# ExtensionConnector.net
KiCad netlist of a schematic drawn in Altium Designer
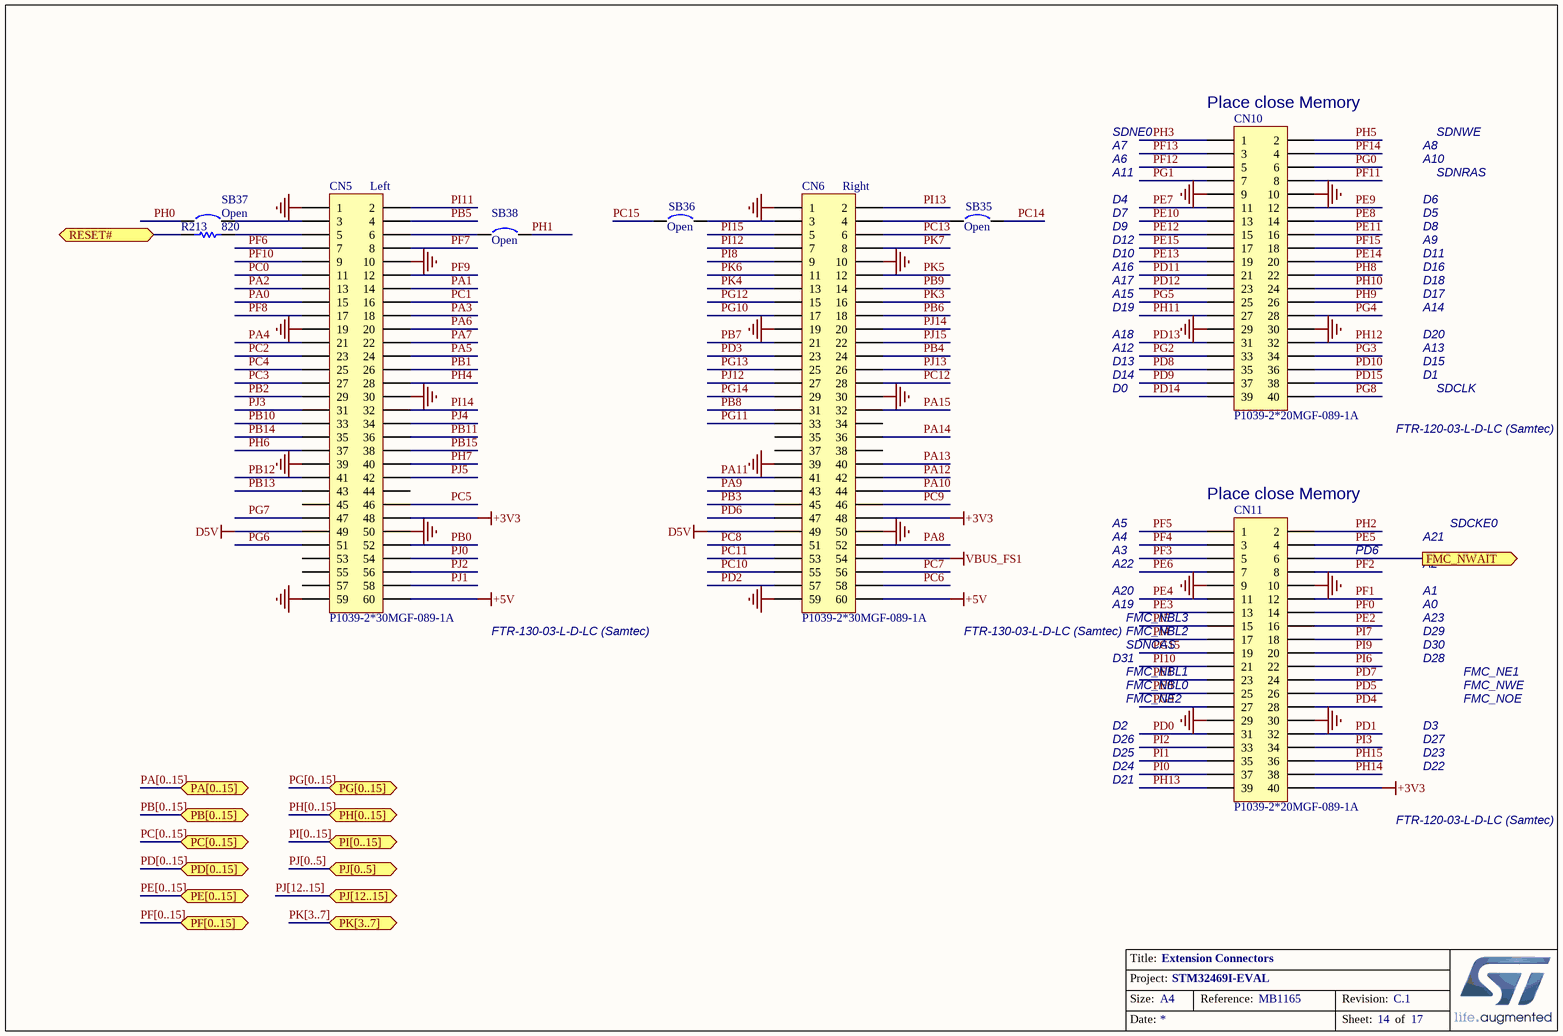
[diagram p0: ExtensionConnector.SchDoc]

(export (version "E")
  (design (tool "Eeschema 10.0.6"))
  (components
    (comp (ref "CN5")
      (value "P1039-2*30MGF-089-1A")
      (footprint "FTR-130-53-L-D-LC")
      (description "Header, 40-Pin, Dual row")
      (fields (field (name "PUBLISHER") "Altium Limited"))
      (libsource (lib "mb1045") (part "FTR-130-53-L-D-LC"))
    )
    (comp (ref "CN6")
      (value "P1039-2*30MGF-089-1A")
      (footprint "FTR-130-53-L-D-LC")
      (description "Header, 40-Pin, Dual row")
      (fields (field (name "PUBLISHER") "Altium Limited"))
      (libsource (lib "mb1045") (part "FTR-130-53-L-D-LC"))
    )
    (comp (ref "CN10")
      (value "P1039-2*20MGF-089-1A")
      (footprint "FTR-120-53-L-D-LC")
      (description "Header, 20-Pin, Dual row")
      (fields (field (name "PUBLISHER") "Altium Limited"))
      (libsource (lib "mb1045") (part "FTR-120-53-L-D-LC"))
    )
    (comp (ref "CN11")
      (value "P1039-2*20MGF-089-1A")
      (footprint "FTR-120-53-L-D-LC")
      (description "Header, 20-Pin, Dual row")
      (fields (field (name "PUBLISHER") "Altium Limited"))
      (libsource (lib "mb1045") (part "FTR-120-53-L-D-LC"))
    )
    (comp (ref "R213")
      (value "820")
      (footprint "0603R")
      (description "Resistor")
      (fields (field (name "PUBLISHER") "Altium Limited"))
      (libsource (lib "Miscellaneous Devices") (part "res1"))
    )
    (comp (ref "SB35")
      (value "Open")
      (footprint "SB_0603")
      (description "Circuit Breaker")
      (fields (field (name "PUBLISHER") "Altium Limited"))
      (libsource (lib "MB1165") (part "Circuit Breaker"))
    )
    (comp (ref "SB36")
      (value "Open")
      (footprint "SB_0603")
      (description "Circuit Breaker")
      (fields (field (name "PUBLISHER") "Altium Limited"))
      (libsource (lib "") (part "Circuit Breaker_1"))
    )
    (comp (ref "SB37")
      (value "Open")
      (footprint "SB_0603")
      (description "Circuit Breaker")
      (fields (field (name "PUBLISHER") "Altium Limited"))
      (libsource (lib "") (part "Circuit Breaker_1"))
    )
    (comp (ref "SB38")
      (value "Open")
      (footprint "SB_0603")
      (description "Circuit Breaker")
      (fields (field (name "PUBLISHER") "Altium Limited"))
      (libsource (lib "MB1165") (part "Circuit Breaker"))
    )
  )
  (nets
    (net (code "1") (name "+3V3") (class "Default")
      (node (ref "CN11") (pin "40") (pinfunction "40_40") (pintype "passive"))
      (node (ref "CN5") (pin "48") (pinfunction "48_48") (pintype "passive"))
      (node (ref "CN6") (pin "48") (pinfunction "48_48") (pintype "passive"))
    )
    (net (code "2") (name "+5V") (class "Default")
      (node (ref "CN5") (pin "60") (pinfunction "60_60") (pintype "passive"))
      (node (ref "CN6") (pin "60") (pinfunction "60_60") (pintype "passive"))
    )
    (net (code "3") (name "/FMC_NWAIT") (class "Default")
      (node (ref "CN11") (pin "6") (pinfunction "6_6") (pintype "passive"))
    )
    (net (code "4") (name "/PA0") (class "Default")
      (node (ref "CN5") (pin "15") (pinfunction "15_15") (pintype "passive"))
    )
    (net (code "5") (name "/PA1") (class "Default")
      (node (ref "CN5") (pin "14") (pinfunction "14_14") (pintype "passive"))
    )
    (net (code "6") (name "/PA2") (class "Default")
      (node (ref "CN5") (pin "13") (pinfunction "13_13") (pintype "passive"))
    )
    (net (code "7") (name "/PA3") (class "Default")
      (node (ref "CN5") (pin "18") (pinfunction "18_18") (pintype "passive"))
    )
    (net (code "8") (name "/PA4") (class "Default")
      (node (ref "CN5") (pin "21") (pinfunction "21_21") (pintype "passive"))
    )
    (net (code "9") (name "/PA5") (class "Default")
      (node (ref "CN5") (pin "24") (pinfunction "24_24") (pintype "passive"))
    )
    (net (code "10") (name "/PA6") (class "Default")
      (node (ref "CN5") (pin "20") (pinfunction "20_20") (pintype "passive"))
    )
    (net (code "11") (name "/PA7") (class "Default")
      (node (ref "CN5") (pin "22") (pinfunction "22_22") (pintype "passive"))
    )
    (net (code "12") (name "/PA8") (class "Default")
      (node (ref "CN6") (pin "52") (pinfunction "52_52") (pintype "passive"))
    )
    (net (code "13") (name "/PA9") (class "Default")
      (node (ref "CN6") (pin "43") (pinfunction "43_43") (pintype "passive"))
    )
    (net (code "14") (name "/PA10") (class "Default")
      (node (ref "CN6") (pin "44") (pinfunction "44_44") (pintype "passive"))
    )
    (net (code "15") (name "/PA11") (class "Default")
      (node (ref "CN6") (pin "41") (pinfunction "41_41") (pintype "passive"))
    )
    (net (code "16") (name "/PA12") (class "Default")
      (node (ref "CN6") (pin "42") (pinfunction "42_42") (pintype "passive"))
    )
    (net (code "17") (name "/PA13") (class "Default")
      (node (ref "CN6") (pin "40") (pinfunction "40_40") (pintype "passive"))
    )
    (net (code "18") (name "/PA14") (class "Default")
      (node (ref "CN6") (pin "36") (pinfunction "36_36") (pintype "passive"))
    )
    (net (code "19") (name "/PA15") (class "Default")
      (node (ref "CN6") (pin "32") (pinfunction "32_32") (pintype "passive"))
    )
    (net (code "21") (name "/PB0") (class "Default")
      (node (ref "CN5") (pin "52") (pinfunction "52_52") (pintype "passive"))
    )
    (net (code "22") (name "/PB1") (class "Default")
      (node (ref "CN5") (pin "26") (pinfunction "26_26") (pintype "passive"))
    )
    (net (code "23") (name "/PB2") (class "Default")
      (node (ref "CN5") (pin "29") (pinfunction "29_29") (pintype "passive"))
    )
    (net (code "24") (name "/PB3") (class "Default")
      (node (ref "CN6") (pin "45") (pinfunction "45_45") (pintype "passive"))
    )
    (net (code "25") (name "/PB4") (class "Default")
      (node (ref "CN6") (pin "24") (pinfunction "24_24") (pintype "passive"))
    )
    (net (code "26") (name "/PB5") (class "Default")
      (node (ref "CN5") (pin "4") (pinfunction "4_4") (pintype "passive"))
    )
    (net (code "27") (name "/PB6") (class "Default")
      (node (ref "CN6") (pin "18") (pinfunction "18_18") (pintype "passive"))
    )
    (net (code "28") (name "/PB7") (class "Default")
      (node (ref "CN6") (pin "21") (pinfunction "21_21") (pintype "passive"))
    )
    (net (code "29") (name "/PB8") (class "Default")
      (node (ref "CN6") (pin "31") (pinfunction "31_31") (pintype "passive"))
    )
    (net (code "30") (name "/PB9") (class "Default")
      (node (ref "CN6") (pin "14") (pinfunction "14_14") (pintype "passive"))
    )
    (net (code "31") (name "/PB10") (class "Default")
      (node (ref "CN5") (pin "33") (pinfunction "33_33") (pintype "passive"))
    )
    (net (code "32") (name "/PB11") (class "Default")
      (node (ref "CN5") (pin "36") (pinfunction "36_36") (pintype "passive"))
    )
    (net (code "33") (name "/PB12") (class "Default")
      (node (ref "CN5") (pin "41") (pinfunction "41_41") (pintype "passive"))
    )
    (net (code "34") (name "/PB13") (class "Default")
      (node (ref "CN5") (pin "43") (pinfunction "43_43") (pintype "passive"))
    )
    (net (code "35") (name "/PB14") (class "Default")
      (node (ref "CN5") (pin "35") (pinfunction "35_35") (pintype "passive"))
    )
    (net (code "36") (name "/PB15") (class "Default")
      (node (ref "CN5") (pin "38") (pinfunction "38_38") (pintype "passive"))
    )
    (net (code "38") (name "/PC0") (class "Default")
      (node (ref "CN5") (pin "11") (pinfunction "11_11") (pintype "passive"))
    )
    (net (code "39") (name "/PC1") (class "Default")
      (node (ref "CN5") (pin "16") (pinfunction "16_16") (pintype "passive"))
    )
    (net (code "40") (name "/PC2") (class "Default")
      (node (ref "CN5") (pin "23") (pinfunction "23_23") (pintype "passive"))
    )
    (net (code "41") (name "/PC3") (class "Default")
      (node (ref "CN5") (pin "27") (pinfunction "27_27") (pintype "passive"))
    )
    (net (code "42") (name "/PC4") (class "Default")
      (node (ref "CN5") (pin "25") (pinfunction "25_25") (pintype "passive"))
    )
    (net (code "43") (name "/PC5") (class "Default")
      (node (ref "CN5") (pin "46") (pinfunction "46_46") (pintype "passive"))
    )
    (net (code "44") (name "/PC6") (class "Default")
      (node (ref "CN6") (pin "58") (pinfunction "58_58") (pintype "passive"))
    )
    (net (code "45") (name "/PC7") (class "Default")
      (node (ref "CN6") (pin "56") (pinfunction "56_56") (pintype "passive"))
    )
    (net (code "46") (name "/PC8") (class "Default")
      (node (ref "CN6") (pin "51") (pinfunction "51_51") (pintype "passive"))
    )
    (net (code "47") (name "/PC9") (class "Default")
      (node (ref "CN6") (pin "46") (pinfunction "46_46") (pintype "passive"))
    )
    (net (code "48") (name "/PC10") (class "Default")
      (node (ref "CN6") (pin "55") (pinfunction "55_55") (pintype "passive"))
    )
    (net (code "49") (name "/PC11") (class "Default")
      (node (ref "CN6") (pin "53") (pinfunction "53_53") (pintype "passive"))
    )
    (net (code "50") (name "/PC12") (class "Default")
      (node (ref "CN6") (pin "28") (pinfunction "28_28") (pintype "passive"))
    )
    (net (code "51") (name "/PC13") (class "Default")
      (node (ref "CN6") (pin "6") (pinfunction "6_6") (pintype "passive"))
    )
    (net (code "52") (name "/PC14") (class "Default")
      (node (ref "SB35") (pin "1") (pinfunction "1_1") (pintype "passive"))
    )
    (net (code "53") (name "/PC15") (class "Default")
      (node (ref "SB36") (pin "1") (pinfunction "1_1") (pintype "passive"))
    )
    (net (code "55") (name "/PD0") (class "Default")
      (node (ref "CN11") (pin "31") (pinfunction "31_31") (pintype "passive"))
    )
    (net (code "56") (name "/PD1") (class "Default")
      (node (ref "CN11") (pin "32") (pinfunction "32_32") (pintype "passive"))
    )
    (net (code "57") (name "/PD2") (class "Default")
      (node (ref "CN6") (pin "57") (pinfunction "57_57") (pintype "passive"))
    )
    (net (code "58") (name "/PD3") (class "Default")
      (node (ref "CN6") (pin "23") (pinfunction "23_23") (pintype "passive"))
    )
    (net (code "59") (name "/PD4") (class "Default")
      (node (ref "CN11") (pin "28") (pinfunction "28_28") (pintype "passive"))
    )
    (net (code "60") (name "/PD5") (class "Default")
      (node (ref "CN11") (pin "26") (pinfunction "26_26") (pintype "passive"))
    )
    (net (code "61") (name "/PD6") (class "Default")
      (node (ref "CN6") (pin "47") (pinfunction "47_47") (pintype "passive"))
    )
    (net (code "62") (name "/PD7") (class "Default")
      (node (ref "CN11") (pin "24") (pinfunction "24_24") (pintype "passive"))
    )
    (net (code "63") (name "/PD8") (class "Default")
      (node (ref "CN10") (pin "35") (pinfunction "35_35") (pintype "passive"))
    )
    (net (code "64") (name "/PD9") (class "Default")
      (node (ref "CN10") (pin "37") (pinfunction "37_37") (pintype "passive"))
    )
    (net (code "65") (name "/PD10") (class "Default")
      (node (ref "CN10") (pin "36") (pinfunction "36_36") (pintype "passive"))
    )
    (net (code "66") (name "/PD11") (class "Default")
      (node (ref "CN10") (pin "21") (pinfunction "21_21") (pintype "passive"))
    )
    (net (code "67") (name "/PD12") (class "Default")
      (node (ref "CN10") (pin "23") (pinfunction "23_23") (pintype "passive"))
    )
    (net (code "68") (name "/PD13") (class "Default")
      (node (ref "CN10") (pin "31") (pinfunction "31_31") (pintype "passive"))
    )
    (net (code "69") (name "/PD14") (class "Default")
      (node (ref "CN10") (pin "39") (pinfunction "39_39") (pintype "passive"))
    )
    (net (code "70") (name "/PD15") (class "Default")
      (node (ref "CN10") (pin "38") (pinfunction "38_38") (pintype "passive"))
    )
    (net (code "72") (name "/PE0") (class "Default")
      (node (ref "CN11") (pin "25") (pinfunction "25_25") (pintype "passive"))
    )
    (net (code "73") (name "/PE1") (class "Default")
      (node (ref "CN11") (pin "23") (pinfunction "23_23") (pintype "passive"))
    )
    (net (code "74") (name "/PE2") (class "Default")
      (node (ref "CN11") (pin "16") (pinfunction "16_16") (pintype "passive"))
    )
    (net (code "75") (name "/PE3") (class "Default")
      (node (ref "CN11") (pin "13") (pinfunction "13_13") (pintype "passive"))
    )
    (net (code "76") (name "/PE4") (class "Default")
      (node (ref "CN11") (pin "11") (pinfunction "11_11") (pintype "passive"))
    )
    (net (code "77") (name "/PE5") (class "Default")
      (node (ref "CN11") (pin "4") (pinfunction "4_4") (pintype "passive"))
    )
    (net (code "78") (name "/PE6") (class "Default")
      (node (ref "CN11") (pin "7") (pinfunction "7_7") (pintype "passive"))
    )
    (net (code "79") (name "/PE7") (class "Default")
      (node (ref "CN10") (pin "11") (pinfunction "11_11") (pintype "passive"))
    )
    (net (code "80") (name "/PE8") (class "Default")
      (node (ref "CN10") (pin "14") (pinfunction "14_14") (pintype "passive"))
    )
    (net (code "81") (name "/PE9") (class "Default")
      (node (ref "CN10") (pin "12") (pinfunction "12_12") (pintype "passive"))
    )
    (net (code "82") (name "/PE10") (class "Default")
      (node (ref "CN10") (pin "13") (pinfunction "13_13") (pintype "passive"))
    )
    (net (code "83") (name "/PE11") (class "Default")
      (node (ref "CN10") (pin "16") (pinfunction "16_16") (pintype "passive"))
    )
    (net (code "84") (name "/PE12") (class "Default")
      (node (ref "CN10") (pin "15") (pinfunction "15_15") (pintype "passive"))
    )
    (net (code "85") (name "/PE13") (class "Default")
      (node (ref "CN10") (pin "19") (pinfunction "19_19") (pintype "passive"))
    )
    (net (code "86") (name "/PE14") (class "Default")
      (node (ref "CN10") (pin "20") (pinfunction "20_20") (pintype "passive"))
    )
    (net (code "87") (name "/PE15") (class "Default")
      (node (ref "CN10") (pin "17") (pinfunction "17_17") (pintype "passive"))
    )
    (net (code "89") (name "/PF0") (class "Default")
      (node (ref "CN11") (pin "14") (pinfunction "14_14") (pintype "passive"))
    )
    (net (code "90") (name "/PF1") (class "Default")
      (node (ref "CN11") (pin "12") (pinfunction "12_12") (pintype "passive"))
    )
    (net (code "91") (name "/PF2") (class "Default")
      (node (ref "CN11") (pin "8") (pinfunction "8_8") (pintype "passive"))
    )
    (net (code "92") (name "/PF3") (class "Default")
      (node (ref "CN11") (pin "5") (pinfunction "5_5") (pintype "passive"))
    )
    (net (code "93") (name "/PF4") (class "Default")
      (node (ref "CN11") (pin "3") (pinfunction "3_3") (pintype "passive"))
    )
    (net (code "94") (name "/PF5") (class "Default")
      (node (ref "CN11") (pin "1") (pinfunction "1_1") (pintype "passive"))
    )
    (net (code "95") (name "/PF6") (class "Default")
      (node (ref "CN5") (pin "7") (pinfunction "7_7") (pintype "passive"))
    )
    (net (code "96") (name "/PF7") (class "Default")
      (node (ref "CN5") (pin "8") (pinfunction "8_8") (pintype "passive"))
    )
    (net (code "97") (name "/PF8") (class "Default")
      (node (ref "CN5") (pin "17") (pinfunction "17_17") (pintype "passive"))
    )
    (net (code "98") (name "/PF9") (class "Default")
      (node (ref "CN5") (pin "12") (pinfunction "12_12") (pintype "passive"))
    )
    (net (code "99") (name "/PF10") (class "Default")
      (node (ref "CN5") (pin "9") (pinfunction "9_9") (pintype "passive"))
    )
    (net (code "100") (name "/PF11") (class "Default")
      (node (ref "CN10") (pin "8") (pinfunction "8_8") (pintype "passive"))
    )
    (net (code "101") (name "/PF12") (class "Default")
      (node (ref "CN10") (pin "5") (pinfunction "5_5") (pintype "passive"))
    )
    (net (code "102") (name "/PF13") (class "Default")
      (node (ref "CN10") (pin "3") (pinfunction "3_3") (pintype "passive"))
    )
    (net (code "103") (name "/PF14") (class "Default")
      (node (ref "CN10") (pin "4") (pinfunction "4_4") (pintype "passive"))
    )
    (net (code "104") (name "/PF15") (class "Default")
      (node (ref "CN10") (pin "18") (pinfunction "18_18") (pintype "passive"))
    )
    (net (code "106") (name "/PG0") (class "Default")
      (node (ref "CN10") (pin "6") (pinfunction "6_6") (pintype "passive"))
    )
    (net (code "107") (name "/PG1") (class "Default")
      (node (ref "CN10") (pin "7") (pinfunction "7_7") (pintype "passive"))
    )
    (net (code "108") (name "/PG2") (class "Default")
      (node (ref "CN10") (pin "33") (pinfunction "33_33") (pintype "passive"))
    )
    (net (code "109") (name "/PG3") (class "Default")
      (node (ref "CN10") (pin "34") (pinfunction "34_34") (pintype "passive"))
    )
    (net (code "110") (name "/PG4") (class "Default")
      (node (ref "CN10") (pin "28") (pinfunction "28_28") (pintype "passive"))
    )
    (net (code "111") (name "/PG5") (class "Default")
      (node (ref "CN10") (pin "25") (pinfunction "25_25") (pintype "passive"))
    )
    (net (code "112") (name "/PG6") (class "Default")
      (node (ref "CN5") (pin "51") (pinfunction "51_51") (pintype "passive"))
    )
    (net (code "113") (name "/PG7") (class "Default")
      (node (ref "CN5") (pin "47") (pinfunction "47_47") (pintype "passive"))
    )
    (net (code "114") (name "/PG8") (class "Default")
      (node (ref "CN10") (pin "40") (pinfunction "40_40") (pintype "passive"))
    )
    (net (code "115") (name "/PG9") (class "Default")
      (node (ref "CN11") (pin "27") (pinfunction "27_27") (pintype "passive"))
    )
    (net (code "116") (name "/PG10") (class "Default")
      (node (ref "CN6") (pin "17") (pinfunction "17_17") (pintype "passive"))
    )
    (net (code "117") (name "/PG11") (class "Default")
      (node (ref "CN6") (pin "33") (pinfunction "33_33") (pintype "passive"))
    )
    (net (code "118") (name "/PG12") (class "Default")
      (node (ref "CN6") (pin "15") (pinfunction "15_15") (pintype "passive"))
    )
    (net (code "119") (name "/PG13") (class "Default")
      (node (ref "CN6") (pin "25") (pinfunction "25_25") (pintype "passive"))
    )
    (net (code "120") (name "/PG14") (class "Default")
      (node (ref "CN6") (pin "29") (pinfunction "29_29") (pintype "passive"))
    )
    (net (code "121") (name "/PG15") (class "Default")
      (node (ref "CN11") (pin "19") (pinfunction "19_19") (pintype "passive"))
    )
    (net (code "123") (name "/PH0") (class "Default")
      (node (ref "SB37") (pin "1") (pinfunction "1_1") (pintype "passive"))
    )
    (net (code "124") (name "/PH1") (class "Default")
      (node (ref "SB38") (pin "1") (pinfunction "1_1") (pintype "passive"))
    )
    (net (code "125") (name "/PH2") (class "Default")
      (node (ref "CN11") (pin "2") (pinfunction "2_2") (pintype "passive"))
    )
    (net (code "126") (name "/PH3") (class "Default")
      (node (ref "CN10") (pin "1") (pinfunction "1_1") (pintype "passive"))
    )
    (net (code "127") (name "/PH4") (class "Default")
      (node (ref "CN5") (pin "28") (pinfunction "28_28") (pintype "passive"))
    )
    (net (code "128") (name "/PH5") (class "Default")
      (node (ref "CN10") (pin "2") (pinfunction "2_2") (pintype "passive"))
    )
    (net (code "129") (name "/PH6") (class "Default")
      (node (ref "CN5") (pin "37") (pinfunction "37_37") (pintype "passive"))
    )
    (net (code "130") (name "/PH7") (class "Default")
      (node (ref "CN5") (pin "40") (pinfunction "40_40") (pintype "passive"))
    )
    (net (code "131") (name "/PH8") (class "Default")
      (node (ref "CN10") (pin "22") (pinfunction "22_22") (pintype "passive"))
    )
    (net (code "132") (name "/PH9") (class "Default")
      (node (ref "CN10") (pin "26") (pinfunction "26_26") (pintype "passive"))
    )
    (net (code "133") (name "/PH10") (class "Default")
      (node (ref "CN10") (pin "24") (pinfunction "24_24") (pintype "passive"))
    )
    (net (code "134") (name "/PH11") (class "Default")
      (node (ref "CN10") (pin "27") (pinfunction "27_27") (pintype "passive"))
    )
    (net (code "135") (name "/PH12") (class "Default")
      (node (ref "CN10") (pin "32") (pinfunction "32_32") (pintype "passive"))
    )
    (net (code "136") (name "/PH13") (class "Default")
      (node (ref "CN11") (pin "39") (pinfunction "39_39") (pintype "passive"))
    )
    (net (code "137") (name "/PH14") (class "Default")
      (node (ref "CN11") (pin "38") (pinfunction "38_38") (pintype "passive"))
    )
    (net (code "138") (name "/PH15") (class "Default")
      (node (ref "CN11") (pin "36") (pinfunction "36_36") (pintype "passive"))
    )
    (net (code "140") (name "/PI0") (class "Default")
      (node (ref "CN11") (pin "37") (pinfunction "37_37") (pintype "passive"))
    )
    (net (code "141") (name "/PI1") (class "Default")
      (node (ref "CN11") (pin "35") (pinfunction "35_35") (pintype "passive"))
    )
    (net (code "142") (name "/PI2") (class "Default")
      (node (ref "CN11") (pin "33") (pinfunction "33_33") (pintype "passive"))
    )
    (net (code "143") (name "/PI3") (class "Default")
      (node (ref "CN11") (pin "34") (pinfunction "34_34") (pintype "passive"))
    )
    (net (code "144") (name "/PI4") (class "Default")
      (node (ref "CN11") (pin "17") (pinfunction "17_17") (pintype "passive"))
    )
    (net (code "145") (name "/PI5") (class "Default")
      (node (ref "CN11") (pin "15") (pinfunction "15_15") (pintype "passive"))
    )
    (net (code "146") (name "/PI6") (class "Default")
      (node (ref "CN11") (pin "22") (pinfunction "22_22") (pintype "passive"))
    )
    (net (code "147") (name "/PI7") (class "Default")
      (node (ref "CN11") (pin "18") (pinfunction "18_18") (pintype "passive"))
    )
    (net (code "148") (name "/PI8") (class "Default")
      (node (ref "CN6") (pin "9") (pinfunction "9_9") (pintype "passive"))
    )
    (net (code "149") (name "/PI9") (class "Default")
      (node (ref "CN11") (pin "20") (pinfunction "20_20") (pintype "passive"))
    )
    (net (code "150") (name "/PI10") (class "Default")
      (node (ref "CN11") (pin "21") (pinfunction "21_21") (pintype "passive"))
    )
    (net (code "151") (name "/PI11") (class "Default")
      (node (ref "CN5") (pin "2") (pinfunction "2_2") (pintype "passive"))
    )
    (net (code "152") (name "/PI12") (class "Default")
      (node (ref "CN6") (pin "7") (pinfunction "7_7") (pintype "passive"))
    )
    (net (code "153") (name "/PI13") (class "Default")
      (node (ref "CN6") (pin "2") (pinfunction "2_2") (pintype "passive"))
    )
    (net (code "154") (name "/PI14") (class "Default")
      (node (ref "CN5") (pin "32") (pinfunction "32_32") (pintype "passive"))
    )
    (net (code "155") (name "/PI15") (class "Default")
      (node (ref "CN6") (pin "5") (pinfunction "5_5") (pintype "passive"))
    )
    (net (code "157") (name "/PJ0") (class "Default")
      (node (ref "CN5") (pin "54") (pinfunction "54_54") (pintype "passive"))
    )
    (net (code "158") (name "/PJ1") (class "Default")
      (node (ref "CN5") (pin "58") (pinfunction "58_58") (pintype "passive"))
    )
    (net (code "159") (name "/PJ2") (class "Default")
      (node (ref "CN5") (pin "56") (pinfunction "56_56") (pintype "passive"))
    )
    (net (code "160") (name "/PJ3") (class "Default")
      (node (ref "CN5") (pin "31") (pinfunction "31_31") (pintype "passive"))
    )
    (net (code "161") (name "/PJ4") (class "Default")
      (node (ref "CN5") (pin "34") (pinfunction "34_34") (pintype "passive"))
    )
    (net (code "162") (name "/PJ5") (class "Default")
      (node (ref "CN5") (pin "42") (pinfunction "42_42") (pintype "passive"))
    )
    (net (code "163") (name "/PJ12") (class "Default")
      (node (ref "CN6") (pin "27") (pinfunction "27_27") (pintype "passive"))
    )
    (net (code "164") (name "/PJ13") (class "Default")
      (node (ref "CN6") (pin "26") (pinfunction "26_26") (pintype "passive"))
    )
    (net (code "165") (name "/PJ14") (class "Default")
      (node (ref "CN6") (pin "20") (pinfunction "20_20") (pintype "passive"))
    )
    (net (code "166") (name "/PJ15") (class "Default")
      (node (ref "CN6") (pin "22") (pinfunction "22_22") (pintype "passive"))
    )
    (net (code "169") (name "/PK3") (class "Default")
      (node (ref "CN6") (pin "16") (pinfunction "16_16") (pintype "passive"))
    )
    (net (code "170") (name "/PK4") (class "Default")
      (node (ref "CN6") (pin "13") (pinfunction "13_13") (pintype "passive"))
    )
    (net (code "171") (name "/PK5") (class "Default")
      (node (ref "CN6") (pin "12") (pinfunction "12_12") (pintype "passive"))
    )
    (net (code "172") (name "/PK6") (class "Default")
      (node (ref "CN6") (pin "11") (pinfunction "11_11") (pintype "passive"))
    )
    (net (code "173") (name "/PK7") (class "Default")
      (node (ref "CN6") (pin "8") (pinfunction "8_8") (pintype "passive"))
    )
    (net (code "175") (name "/RESET#") (class "Default")
      (node (ref "R213") (pin "1") (pinfunction "1_1") (pintype "passive"))
    )
    (net (code "176") (name "D5V") (class "Default")
      (node (ref "CN5") (pin "49") (pinfunction "49_49") (pintype "passive"))
      (node (ref "CN6") (pin "49") (pinfunction "49_49") (pintype "passive"))
    )
    (net (code "177") (name "GND") (class "Default")
      (node (ref "CN10") (pin "10") (pinfunction "10_10") (pintype "passive"))
      (node (ref "CN10") (pin "29") (pinfunction "29_29") (pintype "passive"))
      (node (ref "CN10") (pin "30") (pinfunction "30_30") (pintype "passive"))
      (node (ref "CN10") (pin "9") (pinfunction "9_9") (pintype "passive"))
      (node (ref "CN11") (pin "10") (pinfunction "10_10") (pintype "passive"))
      (node (ref "CN11") (pin "29") (pinfunction "29_29") (pintype "passive"))
      (node (ref "CN11") (pin "30") (pinfunction "30_30") (pintype "passive"))
      (node (ref "CN11") (pin "9") (pinfunction "9_9") (pintype "passive"))
      (node (ref "CN5") (pin "1") (pinfunction "1_1") (pintype "passive"))
      (node (ref "CN5") (pin "10") (pinfunction "10_10") (pintype "passive"))
      (node (ref "CN5") (pin "19") (pinfunction "19_19") (pintype "passive"))
      (node (ref "CN5") (pin "30") (pinfunction "30_30") (pintype "passive"))
      (node (ref "CN5") (pin "39") (pinfunction "39_39") (pintype "passive"))
      (node (ref "CN5") (pin "50") (pinfunction "50_50") (pintype "passive"))
      (node (ref "CN5") (pin "59") (pinfunction "59_59") (pintype "passive"))
      (node (ref "CN6") (pin "1") (pinfunction "1_1") (pintype "passive"))
      (node (ref "CN6") (pin "10") (pinfunction "10_10") (pintype "passive"))
      (node (ref "CN6") (pin "19") (pinfunction "19_19") (pintype "passive"))
      (node (ref "CN6") (pin "30") (pinfunction "30_30") (pintype "passive"))
      (node (ref "CN6") (pin "39") (pinfunction "39_39") (pintype "passive"))
      (node (ref "CN6") (pin "50") (pinfunction "50_50") (pintype "passive"))
      (node (ref "CN6") (pin "59") (pinfunction "59_59") (pintype "passive"))
    )
    (net (code "178") (name "Net-(CN5-Pad3)") (class "Default")
      (node (ref "CN5") (pin "3") (pinfunction "3_3") (pintype "passive"))
      (node (ref "SB37") (pin "2") (pinfunction "2_2") (pintype "passive"))
    )
    (net (code "179") (name "Net-(CN5-Pad5)") (class "Default")
      (node (ref "CN5") (pin "5") (pinfunction "5_5") (pintype "passive"))
      (node (ref "R213") (pin "2") (pinfunction "2_2") (pintype "passive"))
    )
    (net (code "180") (name "Net-(CN5-Pad6)") (class "Default")
      (node (ref "CN5") (pin "6") (pinfunction "6_6") (pintype "passive"))
      (node (ref "SB38") (pin "2") (pinfunction "2_2") (pintype "passive"))
    )
    (net (code "181") (name "Net-(CN6-Pad3)") (class "Default")
      (node (ref "CN6") (pin "3") (pinfunction "3_3") (pintype "passive"))
      (node (ref "SB36") (pin "2") (pinfunction "2_2") (pintype "passive"))
    )
    (net (code "182") (name "Net-(CN6-Pad4)") (class "Default")
      (node (ref "CN6") (pin "4") (pinfunction "4_4") (pintype "passive"))
      (node (ref "SB35") (pin "2") (pinfunction "2_2") (pintype "passive"))
    )
    (net (code "183") (name "VBUS_FS1") (class "Default")
      (node (ref "CN6") (pin "54") (pinfunction "54_54") (pintype "passive"))
    )
    (net (code "184") (name "unconnected-(CN5-Pad44)") (class "Default")
      (node (ref "CN5") (pin "44") (pinfunction "44_44") (pintype "passive"))
    )
    (net (code "185") (name "unconnected-(CN5-Pad45)") (class "Default")
      (node (ref "CN5") (pin "45") (pinfunction "45_45") (pintype "passive"))
    )
    (net (code "186") (name "unconnected-(CN5-Pad53)") (class "Default")
      (node (ref "CN5") (pin "53") (pinfunction "53_53") (pintype "passive"))
    )
    (net (code "187") (name "unconnected-(CN5-Pad55)") (class "Default")
      (node (ref "CN5") (pin "55") (pinfunction "55_55") (pintype "passive"))
    )
    (net (code "188") (name "unconnected-(CN5-Pad57)") (class "Default")
      (node (ref "CN5") (pin "57") (pinfunction "57_57") (pintype "passive"))
    )
    (net (code "189") (name "unconnected-(CN6-Pad34)") (class "Default")
      (node (ref "CN6") (pin "34") (pinfunction "34_34") (pintype "passive"))
    )
    (net (code "190") (name "unconnected-(CN6-Pad35)") (class "Default")
      (node (ref "CN6") (pin "35") (pinfunction "35_35") (pintype "passive"))
    )
    (net (code "191") (name "unconnected-(CN6-Pad37)") (class "Default")
      (node (ref "CN6") (pin "37") (pinfunction "37_37") (pintype "passive"))
    )
    (net (code "192") (name "unconnected-(CN6-Pad38)") (class "Default")
      (node (ref "CN6") (pin "38") (pinfunction "38_38") (pintype "passive"))
    )
  )
)
